# bat-board_rev_2_1.net
KiCad netlist of a schematic drawn in EAGLE
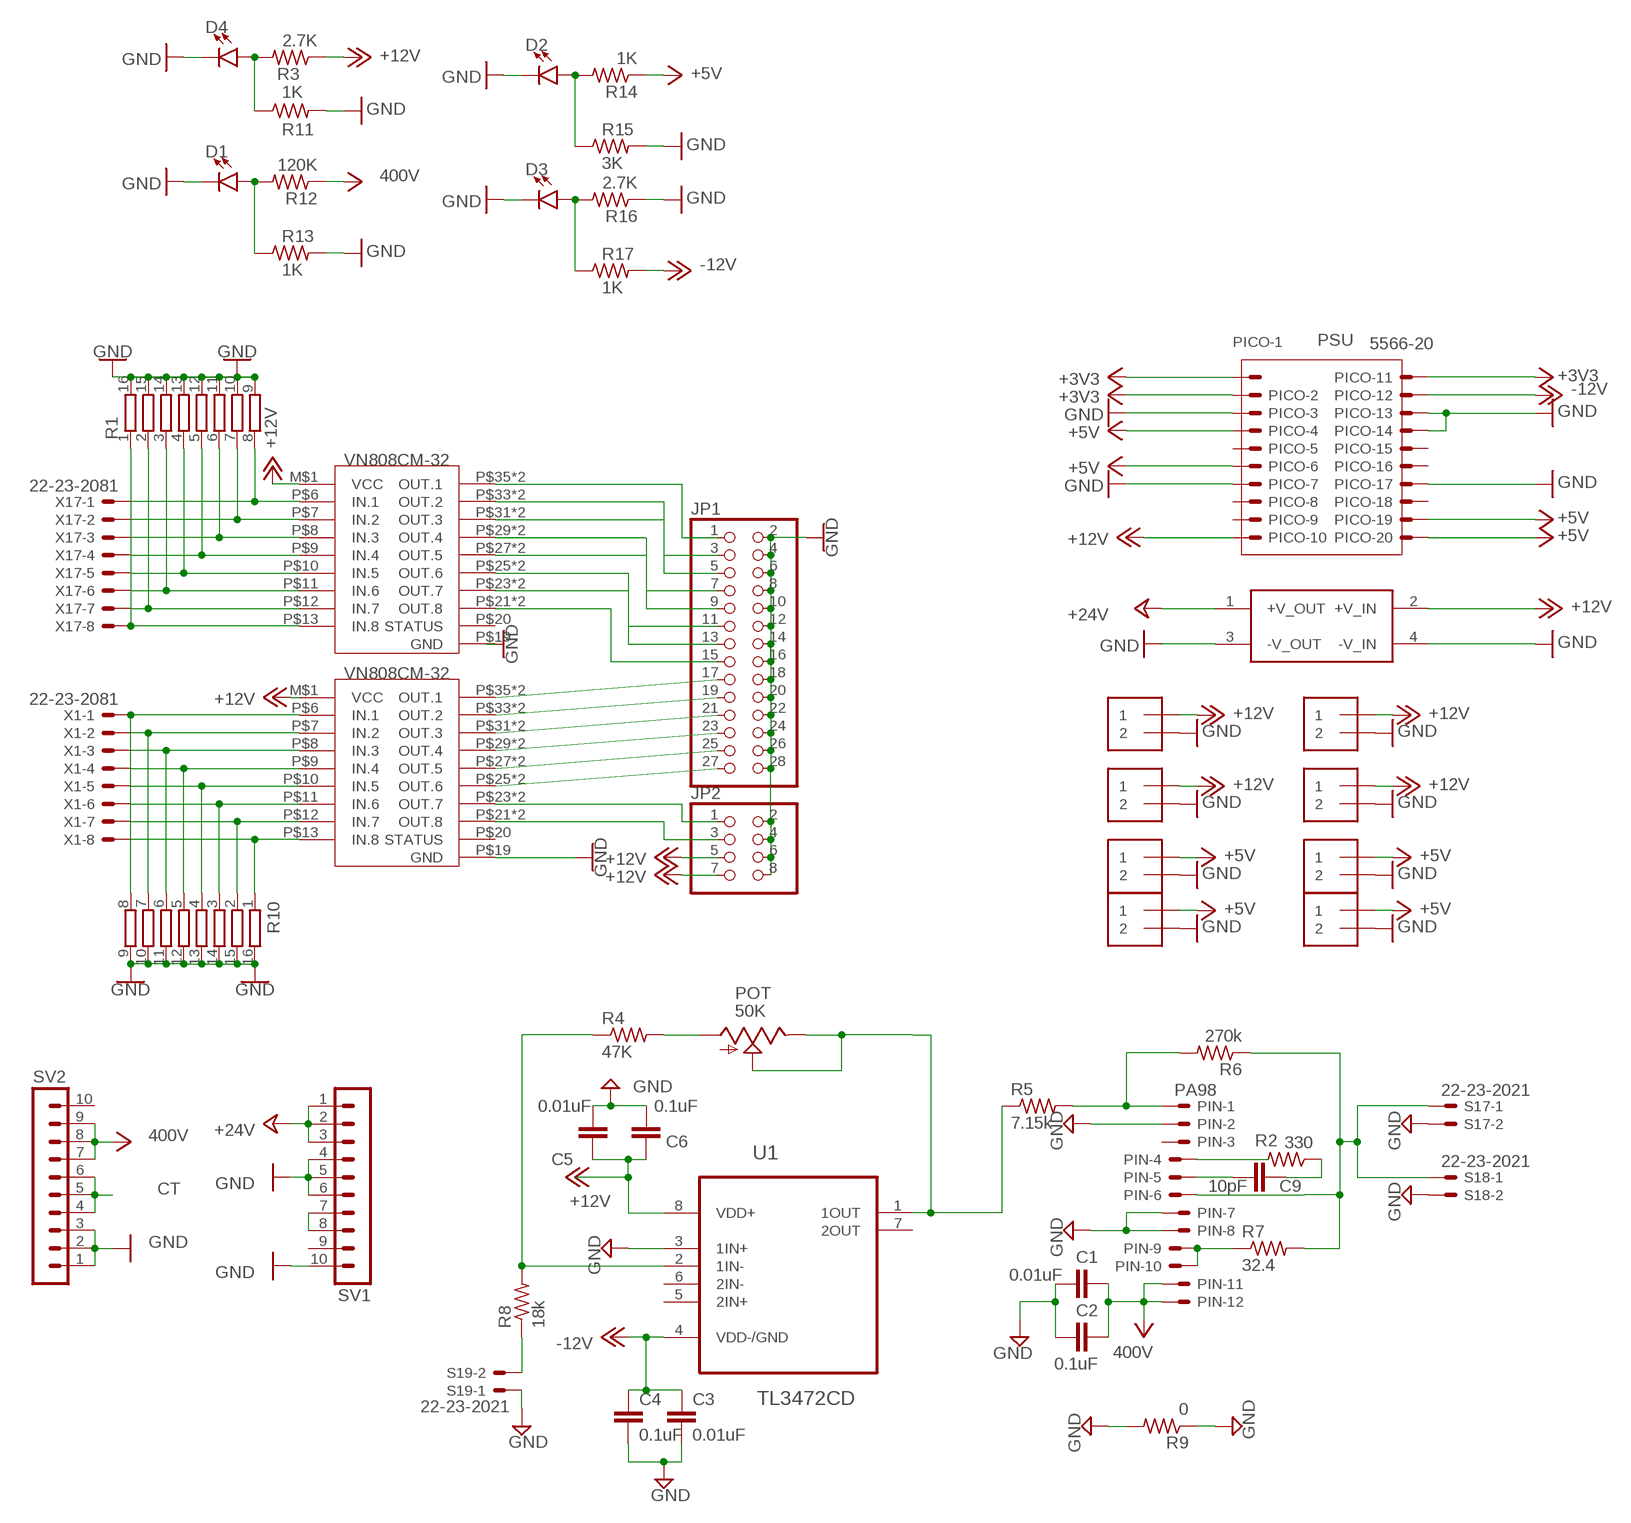
[diagram p0: schematic, sheet 1]

(export (version "E")
  (design (tool "Eeschema 10.0.6"))
  (components
    (comp (ref "$ZX1")
      (value "12_DC-24_DC")
      (footprint "eagle-import:12_DC-24_DC")
      (libsource (lib "eagle-import") (part "12_DC-24_DC"))
    )
    (comp (ref "C1")
      (value "0.01uF")
      (footprint "eagle-import:1206")
      (fields (field (name "MF") "KEMET") (field (name "MPN") "C0805C103K1RACTU"))
      (libsource (lib "eagle-import") (part "1.0UF-1206-50V-10%"))
    )
    (comp (ref "C2")
      (value "0.1uF")
      (footprint "eagle-import:1206")
      (fields (field (name "MF") "KEMET") (field (name "MPN") "C0805C104J5RACTU"))
      (libsource (lib "eagle-import") (part "1.0UF-1206-50V-10%"))
    )
    (comp (ref "C3")
      (value "0.01uF")
      (footprint "eagle-import:1206")
      (fields (field (name "MF") "KEMET") (field (name "MPN") "C0805C103K1RACTU"))
      (libsource (lib "eagle-import") (part "1.0UF-1206-50V-10%"))
    )
    (comp (ref "C4")
      (value "0.1uF")
      (footprint "eagle-import:1206")
      (fields (field (name "MF") "KEMET") (field (name "MPN") "C0805C104J5RACTU"))
      (libsource (lib "eagle-import") (part "1.0UF-1206-50V-10%"))
    )
    (comp (ref "C5")
      (value "0.01uF")
      (footprint "eagle-import:1206")
      (fields (field (name "MF") "KEMET") (field (name "MPN") "C0805C103K1RACTU"))
      (libsource (lib "eagle-import") (part "1.0UF-1206-50V-10%"))
    )
    (comp (ref "C6")
      (value "0.1uF")
      (footprint "eagle-import:1206")
      (fields (field (name "MF") "KEMET") (field (name "MPN") "C0805C104J5RACTU"))
      (libsource (lib "eagle-import") (part "1.0UF-1206-50V-10%"))
    )
    (comp (ref "C9")
      (value "10pF")
      (footprint "eagle-import:1206")
      (fields (field (name "MF") "KEMET") (field (name "MPN") "C0805C479C5GACTU"))
      (libsource (lib "eagle-import") (part "1.0UF-1206-50V-10%"))
    )
    (comp (ref "D1")
      (value "LED1206")
      (footprint "eagle-import:LED-1206")
      (libsource (lib "eagle-import") (part "LED1206"))
    )
    (comp (ref "D2")
      (value "LED1206")
      (footprint "eagle-import:LED-1206")
      (libsource (lib "eagle-import") (part "LED1206"))
    )
    (comp (ref "D3")
      (value "LED1206")
      (footprint "eagle-import:LED-1206")
      (libsource (lib "eagle-import") (part "LED1206"))
    )
    (comp (ref "D4")
      (value "LED1206")
      (footprint "eagle-import:LED-1206")
      (libsource (lib "eagle-import") (part "LED1206"))
    )
    (comp (ref "J1")
      (value "1X2-3.5MM")
      (footprint "eagle-import:1X2-3.5MM")
      (libsource (lib "eagle-import") (part "1X2-3.5MM"))
    )
    (comp (ref "J2")
      (value "1X2-3.5MM")
      (footprint "eagle-import:1X2-3.5MM")
      (libsource (lib "eagle-import") (part "1X2-3.5MM"))
    )
    (comp (ref "J3")
      (value "1X2-3.5MM")
      (footprint "eagle-import:1X2-3.5MM")
      (libsource (lib "eagle-import") (part "1X2-3.5MM"))
    )
    (comp (ref "J4")
      (value "1X2-3.5MM")
      (footprint "eagle-import:1X2-3.5MM")
      (libsource (lib "eagle-import") (part "1X2-3.5MM"))
    )
    (comp (ref "J5")
      (value "1X2-3.5MM")
      (footprint "eagle-import:1X2-3.5MM")
      (libsource (lib "eagle-import") (part "1X2-3.5MM"))
    )
    (comp (ref "J6")
      (value "1X2-3.5MM")
      (footprint "eagle-import:1X2-3.5MM")
      (libsource (lib "eagle-import") (part "1X2-3.5MM"))
    )
    (comp (ref "J7")
      (value "1X2-3.5MM")
      (footprint "eagle-import:1X2-3.5MM")
      (libsource (lib "eagle-import") (part "1X2-3.5MM"))
    )
    (comp (ref "J8")
      (value "1X2-3.5MM")
      (footprint "eagle-import:1X2-3.5MM")
      (libsource (lib "eagle-import") (part "1X2-3.5MM"))
    )
    (comp (ref "JP1")
      (value "PINHD-2X14-CB")
      (footprint "eagle-import:2X14-CLEANBIG")
      (libsource (lib "eagle-import") (part "PINHD-2X14-CB"))
    )
    (comp (ref "JP2")
      (value "PINHD-2X4")
      (footprint "eagle-import:2X04")
      (libsource (lib "eagle-import") (part "PINHD-2X4"))
    )
    (comp (ref "PICO")
      (value "5566-20")
      (footprint "eagle-import:5566-20")
      (libsource (lib "eagle-import") (part "5566-20"))
    )
    (comp (ref "PIN")
      (value "PA98")
      (footprint "eagle-import:22-23-2121")
      (fields
        (field (name "MF") "MOLEX")
        (field (name "MPN") "22-23-2121")
        (field (name "OC_FARNELL") "unknown")
      )
      (libsource (lib "eagle-import") (part "22-23-2121"))
    )
    (comp (ref "POT")
      (value "50K")
      (footprint "eagle-import:3223W")
      (libsource (lib "eagle-import") (part "TRIM_US-3223W"))
    )
    (comp (ref "R1")
      (value "4816P-T01")
      (footprint "eagle-import:4816P")
      (fields (field (name "MF") "BOURNS, INC.") (field (name "MPN") "4816P-T01-684LF"))
      (libsource (lib "eagle-import") (part "4816P-T01"))
    )
    (comp (ref "R2")
      (value "330")
      (footprint "eagle-import:M1206")
      (fields (field (name "MF") "PANASONIC ELECTRONIC COMPONENTS") (field (name "MPN") "ERJ8ENF32R4V"))
      (libsource (lib "eagle-import") (part "R-US_M1206"))
    )
    (comp (ref "R3")
      (value "2.7K")
      (footprint "eagle-import:M1206")
      (fields (field (name "MF") "WELWYN") (field (name "MPN") "WCR0805-18KFI"))
      (libsource (lib "eagle-import") (part "R-US_M1206"))
    )
    (comp (ref "R4")
      (value "47K")
      (footprint "eagle-import:M1206")
      (fields (field (name "MF") "KOA SPEAR ELECTRONICS") (field (name "MPN") "SG73S2ATTD9102F"))
      (libsource (lib "eagle-import") (part "R-US_M1206"))
    )
    (comp (ref "R5")
      (value "7.15k")
      (footprint "eagle-import:M1206")
      (fields (field (name "MF") "VISHAY") (field (name "MPN") "CRCW08057K15FKEA"))
      (libsource (lib "eagle-import") (part "R-US_M1206"))
    )
    (comp (ref "R6")
      (value "270k")
      (footprint "eagle-import:M1206")
      (fields (field (name "MF") "WELWYN") (field (name "MPN") "WCR0805-270KFI"))
      (libsource (lib "eagle-import") (part "R-US_M1206"))
    )
    (comp (ref "R7")
      (value "32.4")
      (footprint "eagle-import:M1206")
      (fields (field (name "MF") "PANASONIC ELECTRONIC COMPONENTS") (field (name "MPN") "ERJ8ENF32R4V"))
      (libsource (lib "eagle-import") (part "R-US_M1206"))
    )
    (comp (ref "R8")
      (value "18k")
      (footprint "eagle-import:M1206")
      (fields (field (name "MF") "WELWYN") (field (name "MPN") "WCR0805-18KFI"))
      (libsource (lib "eagle-import") (part "R-US_M1206"))
    )
    (comp (ref "R9")
      (value "0")
      (footprint "eagle-import:M1206")
      (fields (field (name "MF") "PANASONIC ELECTRONIC COMPONENTS") (field (name "MPN") "ERJ8ENF32R4V"))
      (libsource (lib "eagle-import") (part "R-US_M1206"))
    )
    (comp (ref "R10")
      (value "4816P-T01")
      (footprint "eagle-import:4816P")
      (fields (field (name "MF") "BOURNS, INC.") (field (name "MPN") "4816P-T01-684LF"))
      (libsource (lib "eagle-import") (part "4816P-T01"))
    )
    (comp (ref "R11")
      (value "1K")
      (footprint "eagle-import:M1206")
      (fields (field (name "MF") "WELWYN") (field (name "MPN") "WCR0805-18KFI"))
      (libsource (lib "eagle-import") (part "R-US_M1206"))
    )
    (comp (ref "R12")
      (value "120K")
      (footprint "eagle-import:M1206")
      (fields (field (name "MF") "WELWYN") (field (name "MPN") "WCR0805-18KFI"))
      (libsource (lib "eagle-import") (part "R-US_M1206"))
    )
    (comp (ref "R13")
      (value "1K")
      (footprint "eagle-import:M1206")
      (fields (field (name "MF") "WELWYN") (field (name "MPN") "WCR0805-18KFI"))
      (libsource (lib "eagle-import") (part "R-US_M1206"))
    )
    (comp (ref "R14")
      (value "1K")
      (footprint "eagle-import:M1206")
      (fields (field (name "MF") "WELWYN") (field (name "MPN") "WCR0805-18KFI"))
      (libsource (lib "eagle-import") (part "R-US_M1206"))
    )
    (comp (ref "R15")
      (value "3K")
      (footprint "eagle-import:M1206")
      (fields (field (name "MF") "WELWYN") (field (name "MPN") "WCR0805-18KFI"))
      (libsource (lib "eagle-import") (part "R-US_M1206"))
    )
    (comp (ref "R16")
      (value "2.7K")
      (footprint "eagle-import:M1206")
      (fields (field (name "MF") "WELWYN") (field (name "MPN") "WCR0805-18KFI"))
      (libsource (lib "eagle-import") (part "R-US_M1206"))
    )
    (comp (ref "R17")
      (value "1K")
      (footprint "eagle-import:M1206")
      (fields (field (name "MF") "WELWYN") (field (name "MPN") "WCR0805-18KFI"))
      (libsource (lib "eagle-import") (part "R-US_M1206"))
    )
    (comp (ref "S17")
      (value "22-23-2021")
      (footprint "eagle-import:22-23-2021")
      (fields (field (name "MF") "MOLEX"))
      (libsource (lib "eagle-import") (part "22-23-2021"))
    )
    (comp (ref "S18")
      (value "22-23-2021")
      (footprint "eagle-import:22-23-2021")
      (fields (field (name "MF") "MOLEX"))
      (libsource (lib "eagle-import") (part "22-23-2021"))
    )
    (comp (ref "S19")
      (value "22-23-2021")
      (footprint "eagle-import:22-23-2021")
      (fields (field (name "MF") "MOLEX"))
      (libsource (lib "eagle-import") (part "22-23-2021"))
    )
    (comp (ref "SV1")
      (value "MA10-1")
      (footprint "eagle-import:MA10-1")
      (libsource (lib "eagle-import") (part "MA10-1"))
    )
    (comp (ref "SV2")
      (value "MA10-1")
      (footprint "eagle-import:MA10-1")
      (libsource (lib "eagle-import") (part "MA10-1"))
    )
    (comp (ref "U$3")
      (value "VN808CM-32-E")
      (footprint "eagle-import:PSO36")
      (libsource (lib "eagle-import") (part "VN808CM-32-E"))
    )
    (comp (ref "U$5")
      (value "VN808CM-32-E")
      (footprint "eagle-import:PSO36")
      (libsource (lib "eagle-import") (part "VN808CM-32-E"))
    )
    (comp (ref "U1")
      (value "TL3472CD")
      (footprint "eagle-import:SOIC127P600X175-8N")
      (fields (field (name "MF") "Texas Instruments"))
      (libsource (lib "eagle-import") (part "TL3472CD"))
    )
    (comp (ref "X1")
      (value "22-23-2081")
      (footprint "eagle-import:22-23-2081")
      (fields (field (name "MF") "MOLEX"))
      (libsource (lib "eagle-import") (part "22-23-2081"))
    )
    (comp (ref "X17")
      (value "22-23-2081")
      (footprint "eagle-import:22-23-2081")
      (fields (field (name "MF") "MOLEX"))
      (libsource (lib "eagle-import") (part "22-23-2081"))
    )
  )
  (nets
    (net (code "1") (name "+3V3") (class "Default")
      (node (ref "PICO") (pin "1") (pinfunction "S_1") (pintype "passive"))
      (node (ref "PICO") (pin "11") (pinfunction "S_11") (pintype "passive"))
      (node (ref "PICO") (pin "2") (pinfunction "S_2") (pintype "passive"))
    )
    (net (code "2") (name "+5V") (class "Default")
      (node (ref "J5") (pin "1") (pinfunction "1_1") (pintype "passive"))
      (node (ref "J6") (pin "1") (pinfunction "1_1") (pintype "passive"))
      (node (ref "J7") (pin "1") (pinfunction "1_1") (pintype "passive"))
      (node (ref "J8") (pin "1") (pinfunction "1_1") (pintype "passive"))
      (node (ref "PICO") (pin "19") (pinfunction "S_19") (pintype "passive"))
      (node (ref "PICO") (pin "20") (pinfunction "S_20") (pintype "passive"))
      (node (ref "PICO") (pin "4") (pinfunction "S_4") (pintype "passive"))
      (node (ref "PICO") (pin "6") (pinfunction "S_6") (pintype "passive"))
      (node (ref "R14") (pin "1") (pinfunction "1_1") (pintype "passive"))
    )
    (net (code "3") (name "+12V") (class "Default")
      (node (ref "$ZX1") (pin "2") (pinfunction "+V_IN_2") (pintype "bidirectional"))
      (node (ref "C5") (pin "1") (pinfunction "1_1") (pintype "passive"))
      (node (ref "C6") (pin "1") (pinfunction "1_1") (pintype "passive"))
      (node (ref "J1") (pin "1") (pinfunction "1_1") (pintype "passive"))
      (node (ref "J2") (pin "1") (pinfunction "1_1") (pintype "passive"))
      (node (ref "J3") (pin "1") (pinfunction "1_1") (pintype "passive"))
      (node (ref "J4") (pin "1") (pinfunction "1_1") (pintype "passive"))
      (node (ref "JP2") (pin "5") (pinfunction "5_5") (pintype "passive"))
      (node (ref "JP2") (pin "7") (pinfunction "7_7") (pintype "passive"))
      (node (ref "PICO") (pin "10") (pinfunction "S_10") (pintype "passive"))
      (node (ref "R3") (pin "1") (pinfunction "1_1") (pintype "passive"))
      (node (ref "U$3") (pin "M$1") (pinfunction "VCC_M$1") (pintype "bidirectional"))
      (node (ref "U$5") (pin "M$1") (pinfunction "VCC_M$1") (pintype "bidirectional"))
      (node (ref "U1") (pin "8") (pinfunction "VDD+_8") (pintype "power_in"))
    )
    (net (code "4") (name "+24V") (class "Default")
      (node (ref "$ZX1") (pin "1") (pinfunction "+V_OUT_1") (pintype "bidirectional"))
      (node (ref "SV1") (pin "1") (pinfunction "1_1") (pintype "passive"))
      (node (ref "SV1") (pin "2") (pinfunction "2_2") (pintype "passive"))
      (node (ref "SV1") (pin "3") (pinfunction "3_3") (pintype "passive"))
    )
    (net (code "5") (name "-12V") (class "Default")
      (node (ref "C3") (pin "1") (pinfunction "1_1") (pintype "passive"))
      (node (ref "C4") (pin "1") (pinfunction "1_1") (pintype "passive"))
      (node (ref "PICO") (pin "12") (pinfunction "S_12") (pintype "passive"))
      (node (ref "R17") (pin "2") (pinfunction "2_2") (pintype "passive"))
      (node (ref "U1") (pin "4") (pinfunction "VDD-/GND_4") (pintype "power_in"))
    )
    (net (code "6") (name "/CT") (class "Default")
      (node (ref "SV2") (pin "4") (pinfunction "4_4") (pintype "passive"))
      (node (ref "SV2") (pin "5") (pinfunction "5_5") (pintype "passive"))
      (node (ref "SV2") (pin "6") (pinfunction "6_6") (pintype "passive"))
    )
    (net (code "7") (name "400V") (class "Default")
      (node (ref "C1") (pin "1") (pinfunction "1_1") (pintype "passive"))
      (node (ref "C2") (pin "1") (pinfunction "1_1") (pintype "passive"))
      (node (ref "PIN") (pin "11") (pinfunction "S_11") (pintype "passive"))
      (node (ref "PIN") (pin "12") (pinfunction "S_12") (pintype "passive"))
      (node (ref "R12") (pin "1") (pinfunction "1_1") (pintype "passive"))
      (node (ref "SV2") (pin "7") (pinfunction "7_7") (pintype "passive"))
      (node (ref "SV2") (pin "8") (pinfunction "8_8") (pintype "passive"))
      (node (ref "SV2") (pin "9") (pinfunction "9_9") (pintype "passive"))
    )
    (net (code "8") (name "GND") (class "Default")
      (node (ref "$ZX1") (pin "3") (pinfunction "-V_OUT_3") (pintype "bidirectional"))
      (node (ref "$ZX1") (pin "4") (pinfunction "-V_IN_4") (pintype "bidirectional"))
      (node (ref "C1") (pin "2") (pinfunction "2_2") (pintype "passive"))
      (node (ref "C2") (pin "2") (pinfunction "2_2") (pintype "passive"))
      (node (ref "C3") (pin "2") (pinfunction "2_2") (pintype "passive"))
      (node (ref "C4") (pin "2") (pinfunction "2_2") (pintype "passive"))
      (node (ref "C5") (pin "2") (pinfunction "2_2") (pintype "passive"))
      (node (ref "C6") (pin "2") (pinfunction "2_2") (pintype "passive"))
      (node (ref "D1") (pin "C") (pinfunction "C_C") (pintype "passive"))
      (node (ref "D2") (pin "C") (pinfunction "C_C") (pintype "passive"))
      (node (ref "D3") (pin "C") (pinfunction "C_C") (pintype "passive"))
      (node (ref "D4") (pin "C") (pinfunction "C_C") (pintype "passive"))
      (node (ref "J1") (pin "2") (pinfunction "2_2") (pintype "passive"))
      (node (ref "J2") (pin "2") (pinfunction "2_2") (pintype "passive"))
      (node (ref "J3") (pin "2") (pinfunction "2_2") (pintype "passive"))
      (node (ref "J4") (pin "2") (pinfunction "2_2") (pintype "passive"))
      (node (ref "J5") (pin "2") (pinfunction "2_2") (pintype "passive"))
      (node (ref "J6") (pin "2") (pinfunction "2_2") (pintype "passive"))
      (node (ref "J7") (pin "2") (pinfunction "2_2") (pintype "passive"))
      (node (ref "J8") (pin "2") (pinfunction "2_2") (pintype "passive"))
      (node (ref "JP1") (pin "10") (pinfunction "10_10") (pintype "passive"))
      (node (ref "JP1") (pin "12") (pinfunction "12_12") (pintype "passive"))
      (node (ref "JP1") (pin "14") (pinfunction "14_14") (pintype "passive"))
      (node (ref "JP1") (pin "16") (pinfunction "16_16") (pintype "passive"))
      (node (ref "JP1") (pin "18") (pinfunction "18_18") (pintype "passive"))
      (node (ref "JP1") (pin "2") (pinfunction "2_2") (pintype "passive"))
      (node (ref "JP1") (pin "20") (pinfunction "20_20") (pintype "passive"))
      (node (ref "JP1") (pin "22") (pinfunction "22_22") (pintype "passive"))
      (node (ref "JP1") (pin "24") (pinfunction "24_24") (pintype "passive"))
      (node (ref "JP1") (pin "26") (pinfunction "26_26") (pintype "passive"))
      (node (ref "JP1") (pin "28") (pinfunction "28_28") (pintype "passive"))
      (node (ref "JP1") (pin "4") (pinfunction "4_4") (pintype "passive"))
      (node (ref "JP1") (pin "6") (pinfunction "6_6") (pintype "passive"))
      (node (ref "JP1") (pin "8") (pinfunction "8_8") (pintype "passive"))
      (node (ref "JP2") (pin "2") (pinfunction "2_2") (pintype "passive"))
      (node (ref "JP2") (pin "4") (pinfunction "4_4") (pintype "passive"))
      (node (ref "JP2") (pin "6") (pinfunction "6_6") (pintype "passive"))
      (node (ref "JP2") (pin "8") (pinfunction "8_8") (pintype "passive"))
      (node (ref "PICO") (pin "13") (pinfunction "S_13") (pintype "passive"))
      (node (ref "PICO") (pin "14") (pinfunction "S_14") (pintype "passive"))
      (node (ref "PICO") (pin "17") (pinfunction "S_17") (pintype "passive"))
      (node (ref "PICO") (pin "3") (pinfunction "S_3") (pintype "passive"))
      (node (ref "PICO") (pin "7") (pinfunction "S_7") (pintype "passive"))
      (node (ref "PIN") (pin "2") (pinfunction "S_2") (pintype "passive"))
      (node (ref "PIN") (pin "7") (pinfunction "S_7") (pintype "passive"))
      (node (ref "PIN") (pin "8") (pinfunction "S_8") (pintype "passive"))
      (node (ref "R1") (pin "10") (pinfunction "10_10") (pintype "passive"))
      (node (ref "R1") (pin "11") (pinfunction "11_11") (pintype "passive"))
      (node (ref "R1") (pin "12") (pinfunction "12_12") (pintype "passive"))
      (node (ref "R1") (pin "13") (pinfunction "13_13") (pintype "passive"))
      (node (ref "R1") (pin "14") (pinfunction "14_14") (pintype "passive"))
      (node (ref "R1") (pin "15") (pinfunction "15_15") (pintype "passive"))
      (node (ref "R1") (pin "16") (pinfunction "16_16") (pintype "passive"))
      (node (ref "R1") (pin "9") (pinfunction "9_9") (pintype "passive"))
      (node (ref "R10") (pin "10") (pinfunction "10_10") (pintype "passive"))
      (node (ref "R10") (pin "11") (pinfunction "11_11") (pintype "passive"))
      (node (ref "R10") (pin "12") (pinfunction "12_12") (pintype "passive"))
      (node (ref "R10") (pin "13") (pinfunction "13_13") (pintype "passive"))
      (node (ref "R10") (pin "14") (pinfunction "14_14") (pintype "passive"))
      (node (ref "R10") (pin "15") (pinfunction "15_15") (pintype "passive"))
      (node (ref "R10") (pin "16") (pinfunction "16_16") (pintype "passive"))
      (node (ref "R10") (pin "9") (pinfunction "9_9") (pintype "passive"))
      (node (ref "R11") (pin "2") (pinfunction "2_2") (pintype "passive"))
      (node (ref "R13") (pin "2") (pinfunction "2_2") (pintype "passive"))
      (node (ref "R15") (pin "2") (pinfunction "2_2") (pintype "passive"))
      (node (ref "R16") (pin "1") (pinfunction "1_1") (pintype "passive"))
      (node (ref "R9") (pin "1") (pinfunction "1_1") (pintype "passive"))
      (node (ref "R9") (pin "2") (pinfunction "2_2") (pintype "passive"))
      (node (ref "S17") (pin "2") (pinfunction "S_2") (pintype "passive"))
      (node (ref "S18") (pin "2") (pinfunction "S_2") (pintype "passive"))
      (node (ref "S19") (pin "1") (pinfunction "S_1") (pintype "passive"))
      (node (ref "SV1") (pin "10") (pinfunction "10_10") (pintype "passive"))
      (node (ref "SV1") (pin "4") (pinfunction "4_4") (pintype "passive"))
      (node (ref "SV1") (pin "5") (pinfunction "5_5") (pintype "passive"))
      (node (ref "SV1") (pin "6") (pinfunction "6_6") (pintype "passive"))
      (node (ref "SV2") (pin "1") (pinfunction "1_1") (pintype "passive"))
      (node (ref "SV2") (pin "2") (pinfunction "2_2") (pintype "passive"))
      (node (ref "SV2") (pin "3") (pinfunction "3_3") (pintype "passive"))
      (node (ref "U$3") (pin "P$19") (pinfunction "GND_P$19") (pintype "bidirectional"))
      (node (ref "U$5") (pin "P$19") (pinfunction "GND_P$19") (pintype "bidirectional"))
      (node (ref "U1") (pin "3") (pinfunction "1IN+_3") (pintype "input"))
    )
    (net (code "9") (name "Net-(C9-Pad1)") (class "Default")
      (node (ref "C9") (pin "1") (pinfunction "1_1") (pintype "passive"))
      (node (ref "R2") (pin "1") (pinfunction "1_1") (pintype "passive"))
    )
    (net (code "10") (name "Net-(D1-PadA)") (class "Default")
      (node (ref "D1") (pin "A") (pinfunction "A_A") (pintype "passive"))
      (node (ref "R12") (pin "2") (pinfunction "2_2") (pintype "passive"))
      (node (ref "R13") (pin "1") (pinfunction "1_1") (pintype "passive"))
    )
    (net (code "11") (name "Net-(D2-PadA)") (class "Default")
      (node (ref "D2") (pin "A") (pinfunction "A_A") (pintype "passive"))
      (node (ref "R14") (pin "2") (pinfunction "2_2") (pintype "passive"))
      (node (ref "R15") (pin "1") (pinfunction "1_1") (pintype "passive"))
    )
    (net (code "12") (name "Net-(D3-PadA)") (class "Default")
      (node (ref "D3") (pin "A") (pinfunction "A_A") (pintype "passive"))
      (node (ref "R16") (pin "2") (pinfunction "2_2") (pintype "passive"))
      (node (ref "R17") (pin "1") (pinfunction "1_1") (pintype "passive"))
    )
    (net (code "13") (name "Net-(D4-PadA)") (class "Default")
      (node (ref "D4") (pin "A") (pinfunction "A_A") (pintype "passive"))
      (node (ref "R11") (pin "1") (pinfunction "1_1") (pintype "passive"))
      (node (ref "R3") (pin "2") (pinfunction "2_2") (pintype "passive"))
    )
    (net (code "14") (name "Net-(JP1-Pad1)") (class "Default")
      (node (ref "JP1") (pin "1") (pinfunction "1_1") (pintype "passive"))
      (node (ref "U$5") (pin "P$35") (pinfunction "OUT.1_P$35") (pintype "bidirectional"))
      (node (ref "U$5") (pin "P$36") (pinfunction "OUT.1_P$36") (pintype "bidirectional"))
    )
    (net (code "15") (name "Net-(JP1-Pad3)") (class "Default")
      (node (ref "JP1") (pin "3") (pinfunction "3_3") (pintype "passive"))
      (node (ref "U$5") (pin "P$33") (pinfunction "OUT.2_P$33") (pintype "bidirectional"))
      (node (ref "U$5") (pin "P$34") (pinfunction "OUT.2_P$34") (pintype "bidirectional"))
    )
    (net (code "16") (name "Net-(JP1-Pad5)") (class "Default")
      (node (ref "JP1") (pin "5") (pinfunction "5_5") (pintype "passive"))
      (node (ref "U$5") (pin "P$31") (pinfunction "OUT.3_P$31") (pintype "bidirectional"))
      (node (ref "U$5") (pin "P$32") (pinfunction "OUT.3_P$32") (pintype "bidirectional"))
    )
    (net (code "17") (name "Net-(JP1-Pad7)") (class "Default")
      (node (ref "JP1") (pin "7") (pinfunction "7_7") (pintype "passive"))
      (node (ref "U$5") (pin "P$29") (pinfunction "OUT.4_P$29") (pintype "bidirectional"))
      (node (ref "U$5") (pin "P$30") (pinfunction "OUT.4_P$30") (pintype "bidirectional"))
    )
    (net (code "18") (name "Net-(JP1-Pad9)") (class "Default")
      (node (ref "JP1") (pin "9") (pinfunction "9_9") (pintype "passive"))
      (node (ref "U$5") (pin "P$27") (pinfunction "OUT.5_P$27") (pintype "bidirectional"))
      (node (ref "U$5") (pin "P$28") (pinfunction "OUT.5_P$28") (pintype "bidirectional"))
    )
    (net (code "19") (name "Net-(JP1-Pad11)") (class "Default")
      (node (ref "JP1") (pin "11") (pinfunction "11_11") (pintype "passive"))
      (node (ref "U$5") (pin "P$25") (pinfunction "OUT.6_P$25") (pintype "bidirectional"))
      (node (ref "U$5") (pin "P$26") (pinfunction "OUT.6_P$26") (pintype "bidirectional"))
    )
    (net (code "20") (name "Net-(JP1-Pad13)") (class "Default")
      (node (ref "JP1") (pin "13") (pinfunction "13_13") (pintype "passive"))
      (node (ref "U$5") (pin "P$23") (pinfunction "OUT.7_P$23") (pintype "bidirectional"))
      (node (ref "U$5") (pin "P$24") (pinfunction "OUT.7_P$24") (pintype "bidirectional"))
    )
    (net (code "21") (name "Net-(JP1-Pad15)") (class "Default")
      (node (ref "JP1") (pin "15") (pinfunction "15_15") (pintype "passive"))
      (node (ref "U$5") (pin "P$21") (pinfunction "OUT.8_P$21") (pintype "bidirectional"))
      (node (ref "U$5") (pin "P$22") (pinfunction "OUT.8_P$22") (pintype "bidirectional"))
    )
    (net (code "22") (name "Net-(JP1-Pad17)") (class "Default")
      (node (ref "JP1") (pin "17") (pinfunction "17_17") (pintype "passive"))
      (node (ref "U$3") (pin "P$35") (pinfunction "OUT.1_P$35") (pintype "bidirectional"))
      (node (ref "U$3") (pin "P$36") (pinfunction "OUT.1_P$36") (pintype "bidirectional"))
    )
    (net (code "23") (name "Net-(JP1-Pad19)") (class "Default")
      (node (ref "JP1") (pin "19") (pinfunction "19_19") (pintype "passive"))
      (node (ref "U$3") (pin "P$33") (pinfunction "OUT.2_P$33") (pintype "bidirectional"))
      (node (ref "U$3") (pin "P$34") (pinfunction "OUT.2_P$34") (pintype "bidirectional"))
    )
    (net (code "24") (name "Net-(JP1-Pad21)") (class "Default")
      (node (ref "JP1") (pin "21") (pinfunction "21_21") (pintype "passive"))
      (node (ref "U$3") (pin "P$31") (pinfunction "OUT.3_P$31") (pintype "bidirectional"))
      (node (ref "U$3") (pin "P$32") (pinfunction "OUT.3_P$32") (pintype "bidirectional"))
    )
    (net (code "25") (name "Net-(JP1-Pad23)") (class "Default")
      (node (ref "JP1") (pin "23") (pinfunction "23_23") (pintype "passive"))
      (node (ref "U$3") (pin "P$29") (pinfunction "OUT.4_P$29") (pintype "bidirectional"))
      (node (ref "U$3") (pin "P$30") (pinfunction "OUT.4_P$30") (pintype "bidirectional"))
    )
    (net (code "26") (name "Net-(JP1-Pad25)") (class "Default")
      (node (ref "JP1") (pin "25") (pinfunction "25_25") (pintype "passive"))
      (node (ref "U$3") (pin "P$27") (pinfunction "OUT.5_P$27") (pintype "bidirectional"))
      (node (ref "U$3") (pin "P$28") (pinfunction "OUT.5_P$28") (pintype "bidirectional"))
    )
    (net (code "27") (name "Net-(JP1-Pad27)") (class "Default")
      (node (ref "JP1") (pin "27") (pinfunction "27_27") (pintype "passive"))
      (node (ref "U$3") (pin "P$25") (pinfunction "OUT.6_P$25") (pintype "bidirectional"))
      (node (ref "U$3") (pin "P$26") (pinfunction "OUT.6_P$26") (pintype "bidirectional"))
    )
    (net (code "28") (name "Net-(JP2-Pad1)") (class "Default")
      (node (ref "JP2") (pin "1") (pinfunction "1_1") (pintype "passive"))
      (node (ref "U$3") (pin "P$23") (pinfunction "OUT.7_P$23") (pintype "bidirectional"))
      (node (ref "U$3") (pin "P$24") (pinfunction "OUT.7_P$24") (pintype "bidirectional"))
    )
    (net (code "29") (name "Net-(JP2-Pad3)") (class "Default")
      (node (ref "JP2") (pin "3") (pinfunction "3_3") (pintype "passive"))
      (node (ref "U$3") (pin "P$21") (pinfunction "OUT.8_P$21") (pintype "bidirectional"))
      (node (ref "U$3") (pin "P$22") (pinfunction "OUT.8_P$22") (pintype "bidirectional"))
    )
    (net (code "30") (name "Net-(PINA-S)") (class "Default")
      (node (ref "PIN") (pin "1") (pinfunction "S_1") (pintype "passive"))
      (node (ref "R5") (pin "2") (pinfunction "2_2") (pintype "passive"))
      (node (ref "R6") (pin "2") (pinfunction "2_2") (pintype "passive"))
    )
    (net (code "31") (name "Net-(PINB-S)") (class "Default")
      (node (ref "PIN") (pin "10") (pinfunction "S_10") (pintype "passive"))
      (node (ref "PIN") (pin "9") (pinfunction "S_9") (pintype "passive"))
      (node (ref "R7") (pin "1") (pinfunction "1_1") (pintype "passive"))
    )
    (net (code "32") (name "Net-(PING-S)") (class "Default")
      (node (ref "PIN") (pin "4") (pinfunction "S_4") (pintype "passive"))
      (node (ref "R2") (pin "2") (pinfunction "2_2") (pintype "passive"))
    )
    (net (code "33") (name "Net-(PINH-S)") (class "Default")
      (node (ref "C9") (pin "2") (pinfunction "2_2") (pintype "passive"))
      (node (ref "PIN") (pin "5") (pinfunction "S_5") (pintype "passive"))
    )
    (net (code "34") (name "Net-(PINI-S)") (class "Default")
      (node (ref "PIN") (pin "6") (pinfunction "S_6") (pintype "passive"))
      (node (ref "R6") (pin "1") (pinfunction "1_1") (pintype "passive"))
      (node (ref "R7") (pin "2") (pinfunction "2_2") (pintype "passive"))
      (node (ref "S17") (pin "1") (pinfunction "S_1") (pintype "passive"))
      (node (ref "S18") (pin "1") (pinfunction "S_1") (pintype "passive"))
    )
    (net (code "35") (name "Net-(POT-A)") (class "Default")
      (node (ref "POT") (pin "1") (pinfunction "A_1") (pintype "passive"))
      (node (ref "R4") (pin "2") (pinfunction "2_2") (pintype "passive"))
    )
    (net (code "36") (name "Net-(POT-E)") (class "Default")
      (node (ref "POT") (pin "2") (pinfunction "S_2") (pintype "passive"))
      (node (ref "POT") (pin "3") (pinfunction "E_3") (pintype "passive"))
      (node (ref "R5") (pin "1") (pinfunction "1_1") (pintype "passive"))
      (node (ref "U1") (pin "1") (pinfunction "1OUT_1") (pintype "output"))
    )
    (net (code "37") (name "Net-(S19B-S)") (class "Default")
      (node (ref "R8") (pin "1") (pinfunction "1_1") (pintype "passive"))
      (node (ref "S19") (pin "2") (pinfunction "S_2") (pintype "passive"))
    )
    (net (code "38") (name "Net-(SV1-Pad7)") (class "Default")
      (node (ref "SV1") (pin "7") (pinfunction "7_7") (pintype "passive"))
      (node (ref "SV1") (pin "8") (pinfunction "8_8") (pintype "passive"))
    )
    (net (code "39") (name "Net-(U$3-IN.1)") (class "Default")
      (node (ref "R10") (pin "8") (pinfunction "8_8") (pintype "passive"))
      (node (ref "U$3") (pin "P$6") (pinfunction "IN.1_P$6") (pintype "bidirectional"))
      (node (ref "X1") (pin "1") (pinfunction "S_1") (pintype "passive"))
    )
    (net (code "40") (name "Net-(U$3-IN.2)") (class "Default")
      (node (ref "R10") (pin "7") (pinfunction "7_7") (pintype "passive"))
      (node (ref "U$3") (pin "P$7") (pinfunction "IN.2_P$7") (pintype "bidirectional"))
      (node (ref "X1") (pin "2") (pinfunction "S_2") (pintype "passive"))
    )
    (net (code "41") (name "Net-(U$3-IN.3)") (class "Default")
      (node (ref "R10") (pin "6") (pinfunction "6_6") (pintype "passive"))
      (node (ref "U$3") (pin "P$8") (pinfunction "IN.3_P$8") (pintype "bidirectional"))
      (node (ref "X1") (pin "3") (pinfunction "S_3") (pintype "passive"))
    )
    (net (code "42") (name "Net-(U$3-IN.4)") (class "Default")
      (node (ref "R10") (pin "5") (pinfunction "5_5") (pintype "passive"))
      (node (ref "U$3") (pin "P$9") (pinfunction "IN.4_P$9") (pintype "bidirectional"))
      (node (ref "X1") (pin "4") (pinfunction "S_4") (pintype "passive"))
    )
    (net (code "43") (name "Net-(U$3-IN.5)") (class "Default")
      (node (ref "R10") (pin "4") (pinfunction "4_4") (pintype "passive"))
      (node (ref "U$3") (pin "P$10") (pinfunction "IN.5_P$10") (pintype "bidirectional"))
      (node (ref "X1") (pin "5") (pinfunction "S_5") (pintype "passive"))
    )
    (net (code "44") (name "Net-(U$3-IN.6)") (class "Default")
      (node (ref "R10") (pin "3") (pinfunction "3_3") (pintype "passive"))
      (node (ref "U$3") (pin "P$11") (pinfunction "IN.6_P$11") (pintype "bidirectional"))
      (node (ref "X1") (pin "6") (pinfunction "S_6") (pintype "passive"))
    )
    (net (code "45") (name "Net-(U$3-IN.7)") (class "Default")
      (node (ref "R10") (pin "2") (pinfunction "2_2") (pintype "passive"))
      (node (ref "U$3") (pin "P$12") (pinfunction "IN.7_P$12") (pintype "bidirectional"))
      (node (ref "X1") (pin "7") (pinfunction "S_7") (pintype "passive"))
    )
    (net (code "46") (name "Net-(U$3-IN.8)") (class "Default")
      (node (ref "R10") (pin "1") (pinfunction "1_1") (pintype "passive"))
      (node (ref "U$3") (pin "P$13") (pinfunction "IN.8_P$13") (pintype "bidirectional"))
      (node (ref "X1") (pin "8") (pinfunction "S_8") (pintype "passive"))
    )
    (net (code "47") (name "Net-(U$5-IN.1)") (class "Default")
      (node (ref "R1") (pin "8") (pinfunction "8_8") (pintype "passive"))
      (node (ref "U$5") (pin "P$6") (pinfunction "IN.1_P$6") (pintype "bidirectional"))
      (node (ref "X17") (pin "1") (pinfunction "S_1") (pintype "passive"))
    )
    (net (code "48") (name "Net-(U$5-IN.2)") (class "Default")
      (node (ref "R1") (pin "7") (pinfunction "7_7") (pintype "passive"))
      (node (ref "U$5") (pin "P$7") (pinfunction "IN.2_P$7") (pintype "bidirectional"))
      (node (ref "X17") (pin "2") (pinfunction "S_2") (pintype "passive"))
    )
    (net (code "49") (name "Net-(U$5-IN.3)") (class "Default")
      (node (ref "R1") (pin "6") (pinfunction "6_6") (pintype "passive"))
      (node (ref "U$5") (pin "P$8") (pinfunction "IN.3_P$8") (pintype "bidirectional"))
      (node (ref "X17") (pin "3") (pinfunction "S_3") (pintype "passive"))
    )
    (net (code "50") (name "Net-(U$5-IN.4)") (class "Default")
      (node (ref "R1") (pin "5") (pinfunction "5_5") (pintype "passive"))
      (node (ref "U$5") (pin "P$9") (pinfunction "IN.4_P$9") (pintype "bidirectional"))
      (node (ref "X17") (pin "4") (pinfunction "S_4") (pintype "passive"))
    )
    (net (code "51") (name "Net-(U$5-IN.5)") (class "Default")
      (node (ref "R1") (pin "4") (pinfunction "4_4") (pintype "passive"))
      (node (ref "U$5") (pin "P$10") (pinfunction "IN.5_P$10") (pintype "bidirectional"))
      (node (ref "X17") (pin "5") (pinfunction "S_5") (pintype "passive"))
    )
    (net (code "52") (name "Net-(U$5-IN.6)") (class "Default")
      (node (ref "R1") (pin "3") (pinfunction "3_3") (pintype "passive"))
      (node (ref "U$5") (pin "P$11") (pinfunction "IN.6_P$11") (pintype "bidirectional"))
      (node (ref "X17") (pin "6") (pinfunction "S_6") (pintype "passive"))
    )
    (net (code "53") (name "Net-(U$5-IN.7)") (class "Default")
      (node (ref "R1") (pin "2") (pinfunction "2_2") (pintype "passive"))
      (node (ref "U$5") (pin "P$12") (pinfunction "IN.7_P$12") (pintype "bidirectional"))
      (node (ref "X17") (pin "7") (pinfunction "S_7") (pintype "passive"))
    )
    (net (code "54") (name "Net-(U$5-IN.8)") (class "Default")
      (node (ref "R1") (pin "1") (pinfunction "1_1") (pintype "passive"))
      (node (ref "U$5") (pin "P$13") (pinfunction "IN.8_P$13") (pintype "bidirectional"))
      (node (ref "X17") (pin "8") (pinfunction "S_8") (pintype "passive"))
    )
    (net (code "55") (name "Net-(U1-1IN-)") (class "Default")
      (node (ref "R4") (pin "1") (pinfunction "1_1") (pintype "passive"))
      (node (ref "R8") (pin "2") (pinfunction "2_2") (pintype "passive"))
      (node (ref "U1") (pin "2") (pinfunction "1IN-_2") (pintype "input"))
    )
    (net (code "56") (name "unconnected-(PICOG-S-Pad15)") (class "Default")
      (node (ref "PICO") (pin "15") (pinfunction "S_15") (pintype "passive"))
    )
    (net (code "57") (name "unconnected-(PICOH-S-Pad16)") (class "Default")
      (node (ref "PICO") (pin "16") (pinfunction "S_16") (pintype "passive"))
    )
    (net (code "58") (name "unconnected-(PICOJ-S-Pad18)") (class "Default")
      (node (ref "PICO") (pin "18") (pinfunction "S_18") (pintype "passive"))
    )
    (net (code "59") (name "unconnected-(PICOP-S-Pad5)") (class "Default")
      (node (ref "PICO") (pin "5") (pinfunction "S_5") (pintype "passive"))
    )
    (net (code "60") (name "unconnected-(PICOS-S-Pad8)") (class "Default")
      (node (ref "PICO") (pin "8") (pinfunction "S_8") (pintype "passive"))
    )
    (net (code "61") (name "unconnected-(PICOT-S-Pad9)") (class "Default")
      (node (ref "PICO") (pin "9") (pinfunction "S_9") (pintype "passive"))
    )
    (net (code "62") (name "unconnected-(PINF-S-Pad3)") (class "Default")
      (node (ref "PIN") (pin "3") (pinfunction "S_3") (pintype "passive"))
    )
    (net (code "63") (name "unconnected-(SV1-Pad9)") (class "Default")
      (node (ref "SV1") (pin "9") (pinfunction "9_9") (pintype "passive"))
    )
    (net (code "64") (name "unconnected-(SV2-Pad10)") (class "Default")
      (node (ref "SV2") (pin "10") (pinfunction "10_10") (pintype "passive"))
    )
    (net (code "65") (name "unconnected-(U$3-STATUS-PadP$20)") (class "Default")
      (node (ref "U$3") (pin "P$20") (pinfunction "STATUS_P$20") (pintype "bidirectional"))
    )
    (net (code "66") (name "unconnected-(U$5-STATUS-PadP$20)") (class "Default")
      (node (ref "U$5") (pin "P$20") (pinfunction "STATUS_P$20") (pintype "bidirectional"))
    )
    (net (code "67") (name "unconnected-(U1-2IN+-Pad5)") (class "Default")
      (node (ref "U1") (pin "5") (pinfunction "2IN+_5") (pintype "input"))
    )
    (net (code "68") (name "unconnected-(U1-2IN--Pad6)") (class "Default")
      (node (ref "U1") (pin "6") (pinfunction "2IN-_6") (pintype "input"))
    )
    (net (code "69") (name "unconnected-(U1-2OUT-Pad7)") (class "Default")
      (node (ref "U1") (pin "7") (pinfunction "2OUT_7") (pintype "output"))
    )
  )
)
